# 411_AutoFan_V1_1.net
KiCad netlist of a schematic drawn in EAGLE
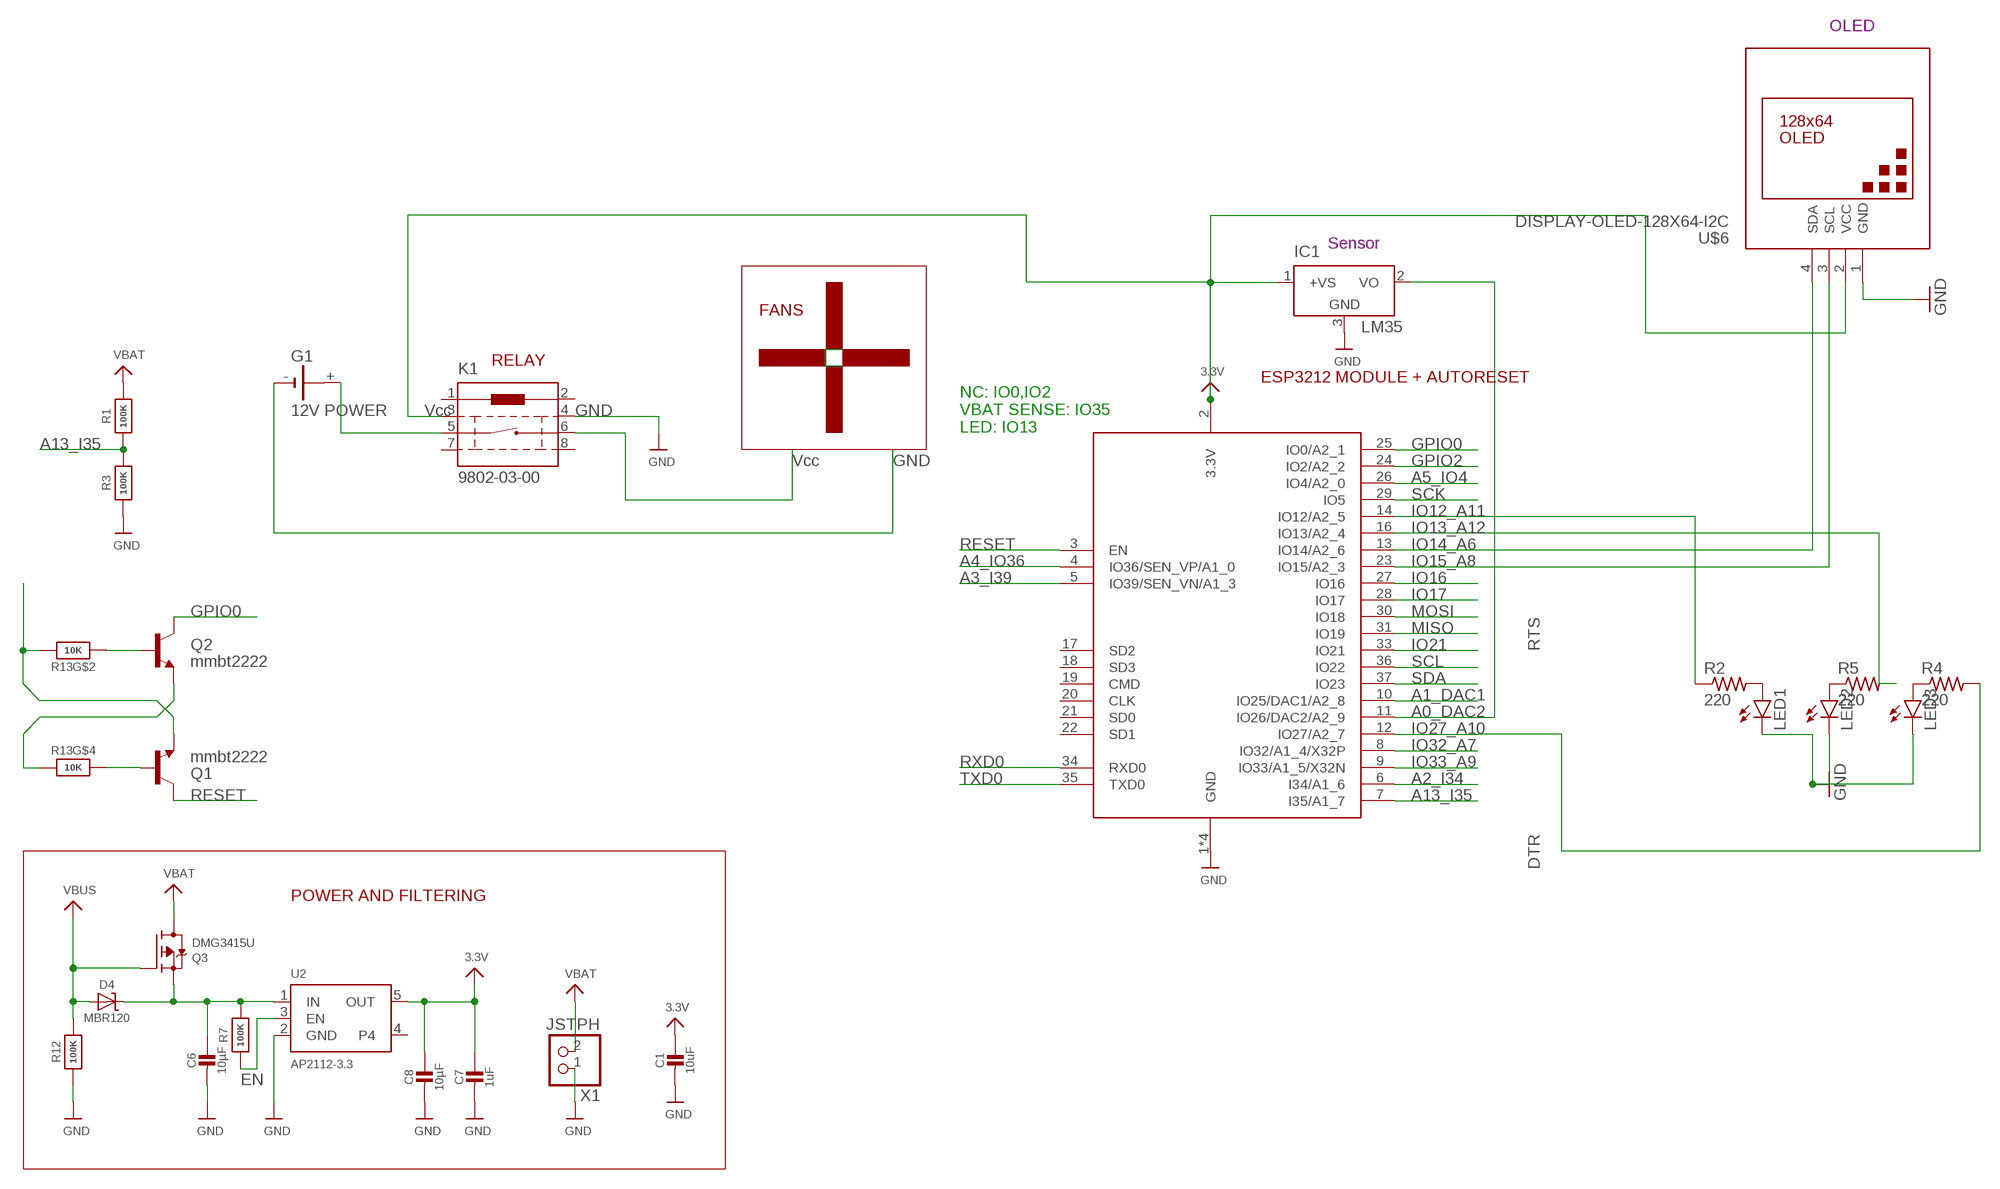
[diagram p0: schematic, sheet 1]

(export (version "E")
  (design (tool "Eeschema 10.0.6"))
  (components
    (comp (ref "C1")
      (value "10uF")
      (footprint "eagle-import:0805-NO")
      (libsource (lib "eagle-import") (part "CAP_CERAMIC0805-NOOUTLINE"))
    )
    (comp (ref "C6")
      (value "10µF")
      (footprint "eagle-import:0805-NO")
      (libsource (lib "eagle-import") (part "CAP_CERAMIC0805-NOOUTLINE"))
    )
    (comp (ref "C7")
      (value "1uF")
      (footprint "eagle-import:0603-NO")
      (libsource (lib "eagle-import") (part "CAP_CERAMIC0603_NO"))
    )
    (comp (ref "C8")
      (value "10µF")
      (footprint "eagle-import:0805-NO")
      (libsource (lib "eagle-import") (part "CAP_CERAMIC0805-NOOUTLINE"))
    )
    (comp (ref "D4")
      (value "MBR120")
      (footprint "eagle-import:SOD-123")
      (libsource (lib "eagle-import") (part "DIODE-SCHOTTKYSOD-123"))
    )
    (comp (ref "G1")
      (value "CR2032V")
      (footprint "eagle-import:CR2032V")
      (libsource (lib "eagle-import") (part "CR2032V"))
    )
    (comp (ref "IC1")
      (value "LM50")
      (footprint "eagle-import:SOT23")
      (libsource (lib "eagle-import") (part "LM50"))
    )
    (comp (ref "K1")
      (value "9802-03-00")
      (footprint "eagle-import:9802-00")
      (libsource (lib "eagle-import") (part "9802-00-03"))
    )
    (comp (ref "LED1")
      (value "LED5MM")
      (footprint "eagle-import:LED5MM")
      (libsource (lib "eagle-import") (part "LED5MM"))
    )
    (comp (ref "LED2")
      (value "LED5MM")
      (footprint "eagle-import:LED5MM")
      (libsource (lib "eagle-import") (part "LED5MM"))
    )
    (comp (ref "LED3")
      (value "LED5MM")
      (footprint "eagle-import:LED5MM")
      (libsource (lib "eagle-import") (part "LED5MM"))
    )
    (comp (ref "Q1")
      (value "mmbt2222")
      (footprint "eagle-import:SOT23-3")
      (libsource (lib "eagle-import") (part "TRANSISTOR_NPNSOT23-3"))
    )
    (comp (ref "Q2")
      (value "mmbt2222")
      (footprint "eagle-import:SOT23-3")
      (libsource (lib "eagle-import") (part "TRANSISTOR_NPNSOT23-3"))
    )
    (comp (ref "Q3")
      (value "DMG3415U")
      (footprint "eagle-import:SOT23-R")
      (libsource (lib "eagle-import") (part "MOSFET-P"))
    )
    (comp (ref "R1")
      (value "100K")
      (footprint "eagle-import:0603-NO")
      (libsource (lib "eagle-import") (part "RESISTOR_0603_NOOUT"))
    )
    (comp (ref "R2")
      (value "220")
      (footprint "eagle-import:0204_7")
      (libsource (lib "eagle-import") (part "R-US_0204/7"))
    )
    (comp (ref "R3")
      (value "100K")
      (footprint "eagle-import:0603-NO")
      (libsource (lib "eagle-import") (part "RESISTOR_0603_NOOUT"))
    )
    (comp (ref "R4")
      (value "220")
      (footprint "eagle-import:0204_7")
      (libsource (lib "eagle-import") (part "R-US_0204/7"))
    )
    (comp (ref "R5")
      (value "220")
      (footprint "eagle-import:0204_7")
      (libsource (lib "eagle-import") (part "R-US_0204/7"))
    )
    (comp (ref "R7")
      (value "100K")
      (footprint "eagle-import:0603-NO")
      (libsource (lib "eagle-import") (part "RESISTOR_0603_NOOUT"))
    )
    (comp (ref "R12")
      (value "100K")
      (footprint "eagle-import:0603-NO")
      (libsource (lib "eagle-import") (part "RESISTOR_0603_NOOUT"))
    )
    (comp (ref "R13")
      (value "10K")
      (footprint "eagle-import:RESPACK_4X0603")
      (libsource (lib "eagle-import") (part "RESISTOR_4PACK"))
    )
    (comp (ref "U$6")
      (value "DISPLAY-OLED-128X64-I2C")
      (footprint "eagle-import:DISPLAY-OLED-128X64-I2C")
      (libsource (lib "eagle-import") (part "DISPLAY-OLED-128X64-I2C"))
    )
    (comp (ref "U2")
      (value "AP2112-3.3")
      (footprint "eagle-import:SOT23-5")
      (libsource (lib "eagle-import") (part "VREG_SOT23-5"))
    )
    (comp (ref "X1")
      (value "JSTPH")
      (footprint "eagle-import:JSTPH2")
      (libsource (lib "eagle-import") (part "CON_JST_PH_2PIN"))
    )
    (comp (ref "X2")
      (value "ESP32_WROOM32_SKINNY")
      (footprint "eagle-import:WROOM32_SKINNY")
      (libsource (lib "eagle-import") (part "ESP32_WROOM32_SKINNY"))
    )
  )
  (nets
    (net (code "1") (name "/A0_DAC2") (class "Default")
      (node (ref "IC1") (pin "2") (pinfunction "VO_2") (pintype "input"))
      (node (ref "X2") (pin "11") (pinfunction "IO26/DAC2/A2_9_11") (pintype "bidirectional"))
    )
    (net (code "2") (name "/A1_DAC1") (class "Default")
      (node (ref "X2") (pin "10") (pinfunction "IO25/DAC1/A2_8_10") (pintype "bidirectional"))
    )
    (net (code "3") (name "/A2_I34") (class "Default")
      (node (ref "X2") (pin "6") (pinfunction "I34/A1_6_6") (pintype "bidirectional"))
    )
    (net (code "4") (name "/A3_I39") (class "Default")
      (node (ref "X2") (pin "5") (pinfunction "IO39/SEN_VN/A1_3_5") (pintype "passive"))
    )
    (net (code "5") (name "/A4_IO36") (class "Default")
      (node (ref "X2") (pin "4") (pinfunction "IO36/SEN_VP/A1_0_4") (pintype "passive"))
    )
    (net (code "6") (name "/A5_IO4") (class "Default")
      (node (ref "X2") (pin "26") (pinfunction "IO4/A2_0_26") (pintype "bidirectional"))
    )
    (net (code "7") (name "/A13_I35") (class "Default")
      (node (ref "R1") (pin "1") (pinfunction "1_1") (pintype "passive"))
      (node (ref "R3") (pin "2") (pinfunction "2_2") (pintype "passive"))
      (node (ref "X2") (pin "7") (pinfunction "I35/A1_7_7") (pintype "bidirectional"))
    )
    (net (code "8") (name "/DTR") (class "Default")
      (node (ref "Q2") (pin "2") (pinfunction "E_2") (pintype "passive"))
      (node (ref "R13") (pin "4") (pinfunction "1_4") (pintype "passive"))
    )
    (net (code "9") (name "/EN") (class "Default")
      (node (ref "R7") (pin "1") (pinfunction "1_1") (pintype "passive"))
      (node (ref "U2") (pin "3") (pinfunction "EN_3") (pintype "input"))
    )
    (net (code "10") (name "/GPIO0") (class "Default")
      (node (ref "Q2") (pin "3") (pinfunction "C_3") (pintype "passive"))
      (node (ref "X2") (pin "25") (pinfunction "IO0/A2_1_25") (pintype "bidirectional"))
    )
    (net (code "11") (name "/GPIO2") (class "Default")
      (node (ref "X2") (pin "24") (pinfunction "IO2/A2_2_24") (pintype "bidirectional"))
    )
    (net (code "12") (name "/IO12_A11") (class "Default")
      (node (ref "R2") (pin "1") (pinfunction "1_1") (pintype "passive"))
      (node (ref "X2") (pin "14") (pinfunction "IO12/A2_5_14") (pintype "bidirectional"))
    )
    (net (code "13") (name "/IO13_A12") (class "Default")
      (node (ref "R5") (pin "2") (pinfunction "2_2") (pintype "passive"))
      (node (ref "X2") (pin "16") (pinfunction "IO13/A2_4_16") (pintype "bidirectional"))
    )
    (net (code "14") (name "/IO14_A6") (class "Default")
      (node (ref "U$6") (pin "4") (pinfunction "SDA_4") (pintype "bidirectional"))
      (node (ref "X2") (pin "13") (pinfunction "IO14/A2_6_13") (pintype "bidirectional"))
    )
    (net (code "15") (name "/IO15_A8") (class "Default")
      (node (ref "U$6") (pin "3") (pinfunction "SCL_3") (pintype "bidirectional"))
      (node (ref "X2") (pin "23") (pinfunction "IO15/A2_3_23") (pintype "bidirectional"))
    )
    (net (code "16") (name "/IO16") (class "Default")
      (node (ref "X2") (pin "27") (pinfunction "IO16_27") (pintype "bidirectional"))
    )
    (net (code "17") (name "/IO17") (class "Default")
      (node (ref "X2") (pin "28") (pinfunction "IO17_28") (pintype "bidirectional"))
    )
    (net (code "18") (name "/IO21") (class "Default")
      (node (ref "X2") (pin "33") (pinfunction "IO21_33") (pintype "bidirectional"))
    )
    (net (code "19") (name "/IO27_A10") (class "Default")
      (node (ref "R4") (pin "2") (pinfunction "2_2") (pintype "passive"))
      (node (ref "X2") (pin "12") (pinfunction "IO27/A2_7_12") (pintype "bidirectional"))
    )
    (net (code "20") (name "/IO32_A7") (class "Default")
      (node (ref "X2") (pin "8") (pinfunction "IO32/A1_4/X32P_8") (pintype "bidirectional"))
    )
    (net (code "21") (name "/IO33_A9") (class "Default")
      (node (ref "X2") (pin "9") (pinfunction "IO33/A1_5/X32N_9") (pintype "bidirectional"))
    )
    (net (code "22") (name "/MISO") (class "Default")
      (node (ref "X2") (pin "31") (pinfunction "IO19_31") (pintype "bidirectional"))
    )
    (net (code "23") (name "/MOSI") (class "Default")
      (node (ref "X2") (pin "30") (pinfunction "IO18_30") (pintype "bidirectional"))
    )
    (net (code "24") (name "/RESET") (class "Default")
      (node (ref "Q1") (pin "3") (pinfunction "C_3") (pintype "passive"))
      (node (ref "X2") (pin "3") (pinfunction "EN_3") (pintype "input"))
    )
    (net (code "25") (name "/RTS") (class "Default")
      (node (ref "Q1") (pin "2") (pinfunction "E_2") (pintype "passive"))
      (node (ref "R13") (pin "7") (pinfunction "2_7") (pintype "passive"))
    )
    (net (code "26") (name "/RXD0") (class "Default")
      (node (ref "X2") (pin "34") (pinfunction "RXD0_34") (pintype "input"))
    )
    (net (code "27") (name "/SCK") (class "Default")
      (node (ref "X2") (pin "29") (pinfunction "IO5_29") (pintype "bidirectional"))
    )
    (net (code "28") (name "/SCL") (class "Default")
      (node (ref "X2") (pin "36") (pinfunction "IO22_36") (pintype "bidirectional"))
    )
    (net (code "29") (name "/SDA") (class "Default")
      (node (ref "X2") (pin "37") (pinfunction "IO23_37") (pintype "bidirectional"))
    )
    (net (code "30") (name "/TXD0") (class "Default")
      (node (ref "X2") (pin "35") (pinfunction "TXD0_35") (pintype "output"))
    )
    (net (code "31") (name "3.3V") (class "Default")
      (node (ref "C1") (pin "1") (pinfunction "1_1") (pintype "passive"))
      (node (ref "C7") (pin "1") (pinfunction "1_1") (pintype "passive"))
      (node (ref "C8") (pin "1") (pinfunction "1_1") (pintype "passive"))
      (node (ref "IC1") (pin "1") (pinfunction "+VS_1") (pintype "input"))
      (node (ref "K1") (pin "3") (pinfunction "3_3") (pintype "passive"))
      (node (ref "U$6") (pin "2") (pinfunction "VCC_2") (pintype "power_in"))
      (node (ref "U2") (pin "5") (pinfunction "OUT_5") (pintype "power_in"))
      (node (ref "X2") (pin "2") (pinfunction "3.3V_2") (pintype "passive"))
    )
    (net (code "32") (name "GND") (class "Default")
      (node (ref "C1") (pin "2") (pinfunction "2_2") (pintype "passive"))
      (node (ref "C6") (pin "2") (pinfunction "2_2") (pintype "passive"))
      (node (ref "C7") (pin "2") (pinfunction "2_2") (pintype "passive"))
      (node (ref "C8") (pin "2") (pinfunction "2_2") (pintype "passive"))
      (node (ref "IC1") (pin "3") (pinfunction "GND_3") (pintype "power_in"))
      (node (ref "K1") (pin "4") (pinfunction "4_4") (pintype "passive"))
      (node (ref "LED1") (pin "K") (pinfunction "C_K") (pintype "passive"))
      (node (ref "LED2") (pin "K") (pinfunction "C_K") (pintype "passive"))
      (node (ref "LED3") (pin "K") (pinfunction "C_K") (pintype "passive"))
      (node (ref "R12") (pin "1") (pinfunction "1_1") (pintype "passive"))
      (node (ref "R3") (pin "1") (pinfunction "1_1") (pintype "passive"))
      (node (ref "U$6") (pin "1") (pinfunction "GND_1") (pintype "power_in"))
      (node (ref "U2") (pin "2") (pinfunction "GND_2") (pintype "power_in"))
      (node (ref "X1") (pin "1") (pinfunction "1_1") (pintype "passive"))
      (node (ref "X2") (pin "1") (pinfunction "GND_1") (pintype "passive"))
      (node (ref "X2") (pin "15") (pinfunction "GND_15") (pintype "passive"))
      (node (ref "X2") (pin "38") (pinfunction "GND_38") (pintype "passive"))
      (node (ref "X2") (pin "P$1") (pinfunction "GND_P$1") (pintype "passive"))
    )
    (net (code "33") (name "Net-(G1-Pad+)") (class "Default")
      (node (ref "G1") (pin "+") (pinfunction "+_+") (pintype "passive"))
      (node (ref "K1") (pin "5") (pinfunction "5_5") (pintype "passive"))
    )
    (net (code "34") (name "Net-(LED1-PadA)") (class "Default")
      (node (ref "LED1") (pin "A") (pinfunction "A_A") (pintype "passive"))
      (node (ref "R2") (pin "2") (pinfunction "2_2") (pintype "passive"))
    )
    (net (code "35") (name "Net-(LED2-PadA)") (class "Default")
      (node (ref "LED2") (pin "A") (pinfunction "A_A") (pintype "passive"))
      (node (ref "R5") (pin "1") (pinfunction "1_1") (pintype "passive"))
    )
    (net (code "36") (name "Net-(LED3-PadA)") (class "Default")
      (node (ref "LED3") (pin "A") (pinfunction "A_A") (pintype "passive"))
      (node (ref "R4") (pin "1") (pinfunction "1_1") (pintype "passive"))
    )
    (net (code "37") (name "Net-(Q1-B)") (class "Default")
      (node (ref "Q1") (pin "1") (pinfunction "B_1") (pintype "passive"))
      (node (ref "R13") (pin "5") (pinfunction "2_5") (pintype "passive"))
    )
    (net (code "38") (name "Net-(Q2-B)") (class "Default")
      (node (ref "Q2") (pin "1") (pinfunction "B_1") (pintype "passive"))
      (node (ref "R13") (pin "2") (pinfunction "1_2") (pintype "passive"))
    )
    (net (code "39") (name "Net-(Q3-S)") (class "Default")
      (node (ref "C6") (pin "1") (pinfunction "1_1") (pintype "passive"))
      (node (ref "D4") (pin "C") (pinfunction "C_C") (pintype "passive"))
      (node (ref "Q3") (pin "2") (pinfunction "S_2") (pintype "passive"))
      (node (ref "R7") (pin "2") (pinfunction "2_2") (pintype "passive"))
      (node (ref "U2") (pin "1") (pinfunction "IN_1") (pintype "power_in"))
    )
    (net (code "40") (name "VBAT") (class "Default")
      (node (ref "Q3") (pin "3") (pinfunction "D_3") (pintype "passive"))
      (node (ref "R1") (pin "2") (pinfunction "2_2") (pintype "passive"))
      (node (ref "X1") (pin "2") (pinfunction "2_2") (pintype "passive"))
    )
    (net (code "41") (name "VBUS") (class "Default")
      (node (ref "D4") (pin "A") (pinfunction "A_A") (pintype "passive"))
      (node (ref "Q3") (pin "1") (pinfunction "G_1") (pintype "passive"))
      (node (ref "R12") (pin "2") (pinfunction "2_2") (pintype "passive"))
    )
    (net (code "42") (name "unconnected-(G1-+-Pad+@1)") (class "Default")
      (node (ref "G1") (pin "+@1") (pinfunction "+_+@1") (pintype "passive"))
    )
    (net (code "43") (name "unconnected-(G1-Pad-)") (class "Default")
      (node (ref "G1") (pin "-") (pinfunction "-_-") (pintype "passive"))
    )
    (net (code "44") (name "unconnected-(K1-Pad1)") (class "Default")
      (node (ref "K1") (pin "1") (pinfunction "1_1") (pintype "passive"))
    )
    (net (code "45") (name "unconnected-(K1-Pad2)") (class "Default")
      (node (ref "K1") (pin "2") (pinfunction "2_2") (pintype "passive"))
    )
    (net (code "46") (name "unconnected-(K1-Pad6)") (class "Default")
      (node (ref "K1") (pin "6") (pinfunction "6_6") (pintype "passive"))
    )
    (net (code "47") (name "unconnected-(K1-Pad7)") (class "Default")
      (node (ref "K1") (pin "7") (pinfunction "7_7") (pintype "passive"))
    )
    (net (code "48") (name "unconnected-(K1-Pad8)") (class "Default")
      (node (ref "K1") (pin "8") (pinfunction "8_8") (pintype "passive"))
    )
    (net (code "49") (name "unconnected-(U2-P4-Pad4)") (class "Default")
      (node (ref "U2") (pin "4") (pinfunction "P4_4") (pintype "bidirectional"))
    )
    (net (code "50") (name "unconnected-(X2-CLK-Pad20)") (class "Default")
      (node (ref "X2") (pin "20") (pinfunction "CLK_20") (pintype "bidirectional"))
    )
    (net (code "51") (name "unconnected-(X2-CMD-Pad19)") (class "Default")
      (node (ref "X2") (pin "19") (pinfunction "CMD_19") (pintype "bidirectional"))
    )
    (net (code "52") (name "unconnected-(X2-SD0-Pad21)") (class "Default")
      (node (ref "X2") (pin "21") (pinfunction "SD0_21") (pintype "bidirectional"))
    )
    (net (code "53") (name "unconnected-(X2-SD1-Pad22)") (class "Default")
      (node (ref "X2") (pin "22") (pinfunction "SD1_22") (pintype "bidirectional"))
    )
    (net (code "54") (name "unconnected-(X2-SD2-Pad17)") (class "Default")
      (node (ref "X2") (pin "17") (pinfunction "SD2_17") (pintype "bidirectional"))
    )
    (net (code "55") (name "unconnected-(X2-SD3-Pad18)") (class "Default")
      (node (ref "X2") (pin "18") (pinfunction "SD3_18") (pintype "bidirectional"))
    )
  )
)
